# TSAL_REV2.net
KiCad netlist of a schematic drawn in Altium Designer
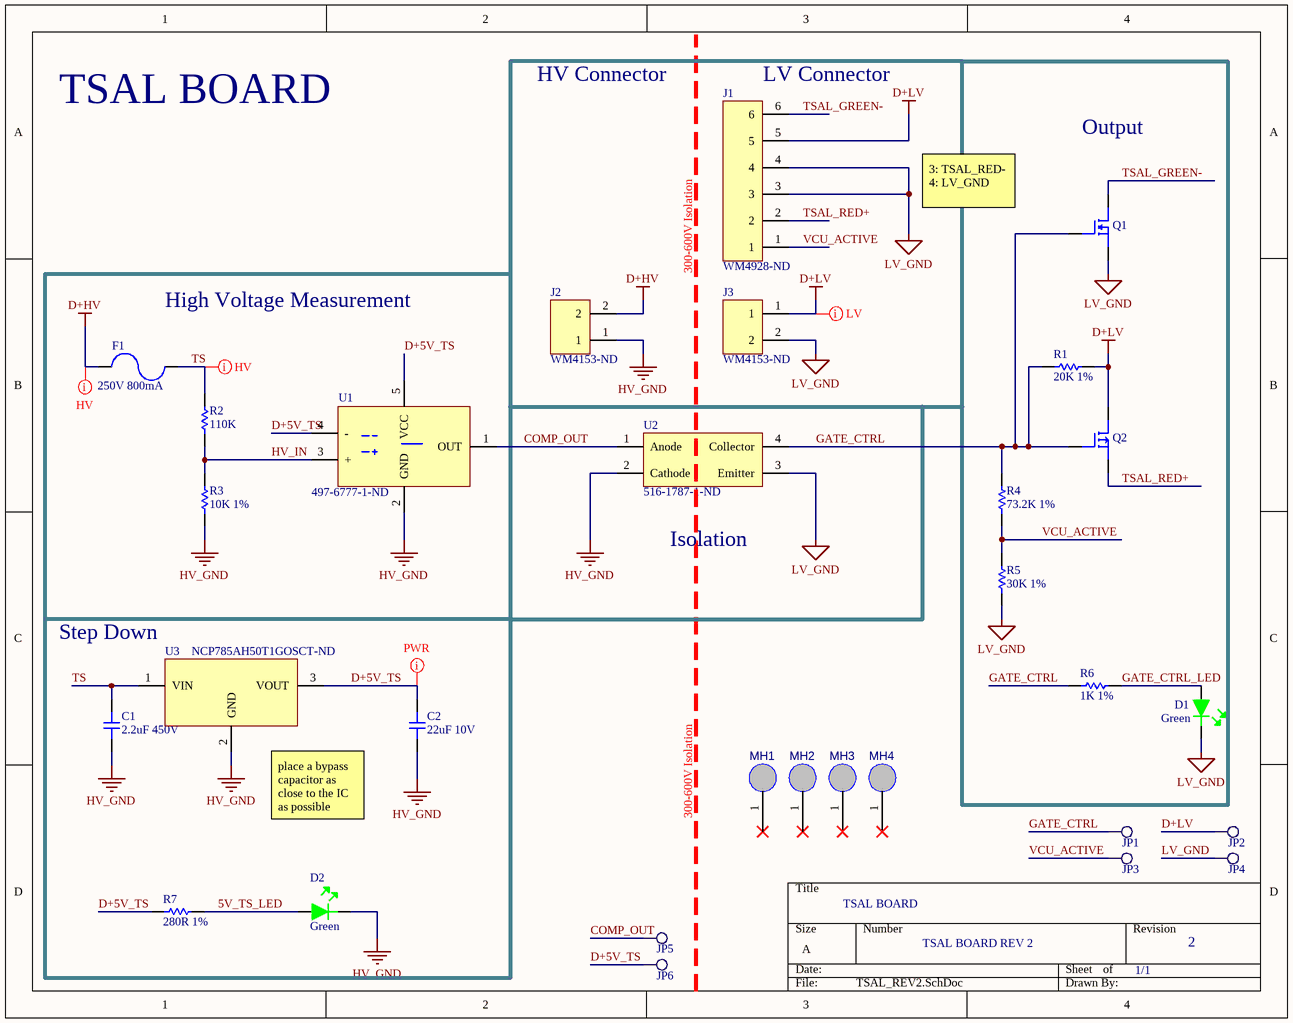
[diagram p0: TSAL_REV2.SchDoc]

(export (version "E")
  (design (tool "Eeschema 10.0.6"))
  (components
    (comp (ref "C1")
      (value "2.2uF 450V")
      (footprint "CAP-2220")
      (description "CAP CER 2.2UF 450V X6S 2220")
      (fields
        (field (name "MANUFACTURER") "TDK")
        (field (name "MANUFACTURER PART NUMBER") "C5750X6S2W225K250KA")
      )
      (libsource (lib "Capacitors") (part "2220-2.2uF-450V"))
    )
    (comp (ref "C2")
      (value "22uF 10V")
      (footprint "CAP-0805")
      (description "CAP CER 22UF 10V X5R 0805")
      (fields
        (field (name "MANUFACTURER") "KEMET")
        (field (name "MANUFACTURER PART NUMBER") "C0805C226M8PACTU")
      )
      (libsource (lib "Capacitors") (part "0805-22uF-10V"))
    )
    (comp (ref "D1")
      (value "Green")
      (footprint "LED-0603")
      (description "LED GREEN CLEAR 0603 SMD")
      (fields
        (field (name "MANUFACTURER") "Wurth Electronics")
        (field (name "MANUFACTURER PART NUMBER") "150060VS75000")
      )
      (libsource (lib "LEDs") (part "LED-Green"))
    )
    (comp (ref "D2")
      (value "Green")
      (footprint "LED-0603")
      (description "LED GREEN CLEAR 0603 SMD")
      (fields
        (field (name "MANUFACTURER") "Wurth Electronics")
        (field (name "MANUFACTURER PART NUMBER") "150060VS75000")
      )
      (libsource (lib "LEDs") (part "LED-Green"))
    )
    (comp (ref "F1")
      (value "250V 800mA")
      (footprint "Fuse-10x3")
      (description "FUSE SMT 3912 FAST 250V 800MA")
      (fields (field (name "MANUFACTURER") "Bel") (field (name "MANUFACTURER PART NUMBER") "0678D0800-02"))
      (libsource (lib "Misc") (part "Fuse 250V-0.8A"))
    )
    (comp (ref "J1")
      (value "WM4928-ND")
      (footprint "6PIN")
      (description "CONN HEADER R/A 6POS 2.54MM")
      (fields (field (name "MANUFACTURER") "Molex") (field (name "MANUFACTURER PART NUMBER") "70553-0040"))
      (libsource (lib "Connectors") (part "6PIN"))
    )
    (comp (ref "J2")
      (value "WM4153-ND")
      (footprint "2PIN")
      (description "CONN HEADER R/A 2POS 2.54MM")
      (fields (field (name "MANUFACTURER") "Molex") (field (name "MANUFACTURER PART NUMBER") "0705530106"))
      (libsource (lib "") (part "2PIN_1"))
    )
    (comp (ref "J3")
      (value "WM4153-ND")
      (footprint "2PIN")
      (description "CONN HEADER R/A 2POS 2.54MM")
      (fields (field (name "MANUFACTURER") "Molex") (field (name "MANUFACTURER PART NUMBER") "0705530106"))
      (libsource (lib "Connectors") (part "2PIN"))
    )
    (comp (ref "JP1")
      (value "Testpoint2")
      (footprint "TP2")
      (description "Single layer pad TP")
      (libsource (lib "Misc") (part "Testpoint2"))
    )
    (comp (ref "JP2")
      (value "Testpoint2")
      (footprint "TP2")
      (description "Single layer pad TP")
      (libsource (lib "Misc") (part "Testpoint2"))
    )
    (comp (ref "JP3")
      (value "Testpoint2")
      (footprint "TP2")
      (description "Single layer pad TP")
      (libsource (lib "Misc") (part "Testpoint2"))
    )
    (comp (ref "JP4")
      (value "Testpoint2")
      (footprint "TP2")
      (description "Single layer pad TP")
      (libsource (lib "Misc") (part "Testpoint2"))
    )
    (comp (ref "JP5")
      (value "Testpoint2")
      (footprint "TP2")
      (description "Single layer pad TP")
      (libsource (lib "Misc") (part "Testpoint2"))
    )
    (comp (ref "JP6")
      (value "Testpoint2")
      (footprint "TP2")
      (description "Single layer pad TP")
      (libsource (lib "Misc") (part "Testpoint2"))
    )
    (comp (ref "MH1")
      (value "MountingHole")
      (footprint "MH4.2MM")
      (description "Mounting hole, 4.2mm")
      (libsource (lib "New_Parts") (part "MH4.2mm"))
    )
    (comp (ref "MH2")
      (value "MountingHole")
      (footprint "MH4.2MM")
      (description "Mounting hole, 4.2mm")
      (libsource (lib "New_Parts") (part "MH4.2mm"))
    )
    (comp (ref "MH3")
      (value "MountingHole")
      (footprint "MH4.2MM")
      (description "Mounting hole, 4.2mm")
      (libsource (lib "New_Parts") (part "MH4.2mm"))
    )
    (comp (ref "MH4")
      (value "MountingHole")
      (footprint "MH4.2MM")
      (description "Mounting hole, 4.2mm")
      (libsource (lib "New_Parts") (part "MH4.2mm"))
    )
    (comp (ref "Q1")
      (value "IPD50N06S4L12ATMA2CT-ND")
      (footprint "DPAK-TO252")
      (description "MOSFET N-CH 60V 50A TO252-3")
      (fields
        (field (name "MANUFACTURER") "Infineon")
        (field (name "MANUFACTURER PART NUMBER") "IPD50N06S4L12ATMA2")
      )
      (libsource (lib "Transistors") (part "N-FET-60V-50A"))
    )
    (comp (ref "Q2")
      (value "NTD2955T4GOSCT-ND")
      (footprint "DPAK-TO252")
      (description "MOSFET P-CH 60V 12A DPAK")
      (fields
        (field (name "MANUFACTURER") "ON Semiconductor")
        (field (name "MANUFACTURER PART NUMBER") "NTD2955T4G")
      )
      (libsource (lib "Transistors") (part "P-FET-60V-12A"))
    )
    (comp (ref "R1")
      (value "20K 1%")
      (footprint "RES-0603")
      (description "RES SMD 20K OHM 1% 1/10W 0603")
      (fields
        (field (name "MANUFACTURER") "Yageo")
        (field (name "MANUFACTURER PART NUMBER") "RC0603FR-0720KL")
      )
      (libsource (lib "Resistors") (part "0603-20KR"))
    )
    (comp (ref "R2")
      (value "110K")
      (footprint "RES-0805")
      (description "RES SMD 110K OHM 1% 1/8W 0805")
      (fields
        (field (name "MANUFACTURER") "Yageo")
        (field (name "MANUFACTURER PART NUMBER") "RC0805FR-07110KL")
      )
      (libsource (lib "Resistors") (part "0805-110KR"))
    )
    (comp (ref "R3")
      (value "10K 1%")
      (footprint "RES-0805")
      (description "RES SMD 10K OHM 1% 1/8W 0805")
      (fields
        (field (name "MANUFACTURER") "Yageo")
        (field (name "MANUFACTURER PART NUMBER") "RC0805FR-0710KL")
      )
      (libsource (lib "Resistors") (part "0805-10KR"))
    )
    (comp (ref "R4")
      (value "73.2K 1%")
      (footprint "RES-0603")
      (description "RES SMD 73.2K OHM 1% 1/10W 0603")
      (fields
        (field (name "MANUFACTURER") "Yageo")
        (field (name "MANUFACTURER PART NUMBER") "RC0603FR-0773K2L")
      )
      (libsource (lib "Resistors") (part "0603-73.2KR"))
    )
    (comp (ref "R5")
      (value "30K 1%")
      (footprint "RES-0603")
      (description "RES SMD 30K OHM 1% 1/10W 0603")
      (fields
        (field (name "MANUFACTURER") "Yageo")
        (field (name "MANUFACTURER PART NUMBER") "RC0603FR-0730KL")
      )
      (libsource (lib "Resistors") (part "0603-30KR"))
    )
    (comp (ref "R6")
      (value "1K 1%")
      (footprint "RES-0603")
      (description "RES SMD 1K OHM 1% 1/10W 0603")
      (fields
        (field (name "MANUFACTURER") "Vishay Dale")
        (field (name "MANUFACTURER PART NUMBER") "CRCW06031K00FKEA")
      )
      (libsource (lib "Resistors") (part "0603-1KR"))
    )
    (comp (ref "R7")
      (value "280R 1%")
      (footprint "RES-0603")
      (description "RES SMD 280 OHM 1% 1/10W 0603")
      (fields
        (field (name "MANUFACTURER") "Yageo")
        (field (name "MANUFACTURER PART NUMBER") "RC0603FR-07280RL")
      )
      (libsource (lib "Resistors") (part "0603-280R"))
    )
    (comp (ref "U1")
      (value "497-6777-1-ND")
      (footprint "SOT-23-5")
      (description "IC COMPARATOR R-R MCRPWR SOT23-5")
      (fields
        (field (name "MANUFACTURER") "STMicroelectronics")
        (field (name "MANUFACTURER PART NUMBER") "TS861ILT")
      )
      (libsource (lib "Logic") (part "Compare-TS861ILT"))
    )
    (comp (ref "U2")
      (value "516-1787-1-ND")
      (footprint "4-SSOP")
      (description "OPTOISO 3.75KV TRANS 4MINIFLAT")
      (fields
        (field (name "MANUFACTURER") "Broadcom Avago")
        (field (name "MANUFACTURER PART NUMBER") "HCPL-181-00BE")
      )
      (libsource (lib "ICs") (part "OPTO-ISO-3.75kV"))
    )
    (comp (ref "U3")
      (value "NCP785AH50T1GOSCT-ND")
      (footprint "SOT-89")
      (description "IC REG LINEAR 5V 10MA SOT89-3")
      (fields
        (field (name "MANUFACTURER") "ON Semiconductor")
        (field (name "MANUFACTURER PART NUMBER") "NCP785AH120T1G")
      )
      (libsource (lib "Power") (part "LDO-12V-10mA"))
    )
  )
  (nets
    (net (code "1") (name "/5V_TS_LED") (class "Default")
      (node (ref "D2") (pin "1") (pinfunction "1_1") (pintype "passive"))
      (node (ref "R7") (pin "2") (pinfunction "2_2") (pintype "passive"))
    )
    (net (code "2") (name "/COMP_OUT") (class "Default")
      (node (ref "JP5") (pin "1") (pinfunction "1_1") (pintype "passive"))
      (node (ref "U1") (pin "1") (pinfunction "OUT_1") (pintype "passive"))
      (node (ref "U2") (pin "1") (pinfunction "Anode_1") (pintype "passive"))
    )
    (net (code "3") (name "/D+5V_TS") (class "Default")
      (node (ref "C2") (pin "2") (pinfunction "2_2") (pintype "passive"))
      (node (ref "JP6") (pin "1") (pinfunction "1_1") (pintype "passive"))
      (node (ref "R7") (pin "1") (pinfunction "1_1") (pintype "passive"))
      (node (ref "U1") (pin "4") (pinfunction "-_4") (pintype "passive"))
      (node (ref "U1") (pin "5") (pinfunction "VCC_5") (pintype "passive"))
      (node (ref "U3") (pin "3") (pinfunction "VOUT_3") (pintype "passive"))
    )
    (net (code "4") (name "/GATE_CTRL") (class "Default")
      (node (ref "JP1") (pin "1") (pinfunction "1_1") (pintype "passive"))
      (node (ref "Q1") (pin "1") (pinfunction "1_1") (pintype "passive"))
      (node (ref "Q2") (pin "1") (pinfunction "1_1") (pintype "passive"))
      (node (ref "R1") (pin "1") (pinfunction "1_1") (pintype "passive"))
      (node (ref "R4") (pin "2") (pinfunction "2_2") (pintype "passive"))
      (node (ref "R6") (pin "1") (pinfunction "1_1") (pintype "passive"))
      (node (ref "U2") (pin "4") (pinfunction "Collector_4") (pintype "passive"))
    )
    (net (code "5") (name "/GATE_CTRL_LED") (class "Default")
      (node (ref "D1") (pin "1") (pinfunction "1_1") (pintype "passive"))
      (node (ref "R6") (pin "2") (pinfunction "2_2") (pintype "passive"))
    )
    (net (code "6") (name "/HV_IN") (class "Default")
      (node (ref "R2") (pin "1") (pinfunction "1_1") (pintype "passive"))
      (node (ref "R3") (pin "2") (pinfunction "2_2") (pintype "passive"))
      (node (ref "U1") (pin "3") (pinfunction "+_3") (pintype "passive"))
    )
    (net (code "7") (name "/TS") (class "Default")
      (node (ref "C1") (pin "1") (pinfunction "1_1") (pintype "passive"))
      (node (ref "F1") (pin "2") (pinfunction "2_2") (pintype "passive"))
      (node (ref "R2") (pin "2") (pinfunction "2_2") (pintype "passive"))
      (node (ref "U3") (pin "1") (pinfunction "VIN_1") (pintype "passive"))
    )
    (net (code "8") (name "/TSAL_GREEN-") (class "Default")
      (node (ref "J1") (pin "6") (pinfunction "6_6") (pintype "passive"))
      (node (ref "Q1") (pin "2") (pinfunction "2_2") (pintype "passive"))
    )
    (net (code "9") (name "/TSAL_RED+") (class "Default")
      (node (ref "J1") (pin "2") (pinfunction "2_2") (pintype "passive"))
      (node (ref "Q2") (pin "3") (pinfunction "3_3") (pintype "passive"))
    )
    (net (code "10") (name "/VCU_ACTIVE") (class "Default")
      (node (ref "J1") (pin "1") (pinfunction "1_1") (pintype "passive"))
      (node (ref "JP3") (pin "1") (pinfunction "1_1") (pintype "passive"))
      (node (ref "R4") (pin "1") (pinfunction "1_1") (pintype "passive"))
      (node (ref "R5") (pin "2") (pinfunction "2_2") (pintype "passive"))
    )
    (net (code "11") (name "D+HV") (class "Default")
      (node (ref "F1") (pin "1") (pinfunction "1_1") (pintype "passive"))
      (node (ref "J2") (pin "2") (pinfunction "2_2") (pintype "passive"))
    )
    (net (code "12") (name "D+LV") (class "Default")
      (node (ref "J1") (pin "5") (pinfunction "5_5") (pintype "passive"))
      (node (ref "J3") (pin "1") (pinfunction "1_1") (pintype "passive"))
      (node (ref "JP2") (pin "1") (pinfunction "1_1") (pintype "passive"))
      (node (ref "Q2") (pin "2") (pinfunction "2_2") (pintype "passive"))
      (node (ref "R1") (pin "2") (pinfunction "2_2") (pintype "passive"))
    )
    (net (code "13") (name "HV_GND") (class "Default")
      (node (ref "C1") (pin "2") (pinfunction "2_2") (pintype "passive"))
      (node (ref "C2") (pin "1") (pinfunction "1_1") (pintype "passive"))
      (node (ref "D2") (pin "2") (pinfunction "2_2") (pintype "passive"))
      (node (ref "J2") (pin "1") (pinfunction "1_1") (pintype "passive"))
      (node (ref "R3") (pin "1") (pinfunction "1_1") (pintype "passive"))
      (node (ref "U1") (pin "2") (pinfunction "GND_2") (pintype "passive"))
      (node (ref "U2") (pin "2") (pinfunction "Cathode_2") (pintype "passive"))
      (node (ref "U3") (pin "2") (pinfunction "GND_2") (pintype "passive"))
    )
    (net (code "14") (name "LV_GND") (class "Default")
      (node (ref "D1") (pin "2") (pinfunction "2_2") (pintype "passive"))
      (node (ref "J1") (pin "3") (pinfunction "3_3") (pintype "passive"))
      (node (ref "J1") (pin "4") (pinfunction "4_4") (pintype "passive"))
      (node (ref "J3") (pin "2") (pinfunction "2_2") (pintype "passive"))
      (node (ref "JP4") (pin "1") (pinfunction "1_1") (pintype "passive"))
      (node (ref "Q1") (pin "3") (pinfunction "3_3") (pintype "passive"))
      (node (ref "R5") (pin "1") (pinfunction "1_1") (pintype "passive"))
      (node (ref "U2") (pin "3") (pinfunction "Emitter_3") (pintype "passive"))
    )
    (net (code "15") (name "unconnected-(MH1-Pad1)") (class "Default")
      (node (ref "MH1") (pin "1") (pintype "passive+no_connect"))
    )
    (net (code "16") (name "unconnected-(MH2-Pad1)") (class "Default")
      (node (ref "MH2") (pin "1") (pintype "passive+no_connect"))
    )
    (net (code "17") (name "unconnected-(MH3-Pad1)") (class "Default")
      (node (ref "MH3") (pin "1") (pintype "passive+no_connect"))
    )
    (net (code "18") (name "unconnected-(MH4-Pad1)") (class "Default")
      (node (ref "MH4") (pin "1") (pintype "passive+no_connect"))
    )
  )
)
